# PowerSupply.net
KiCad netlist of a schematic drawn in Altium Designer
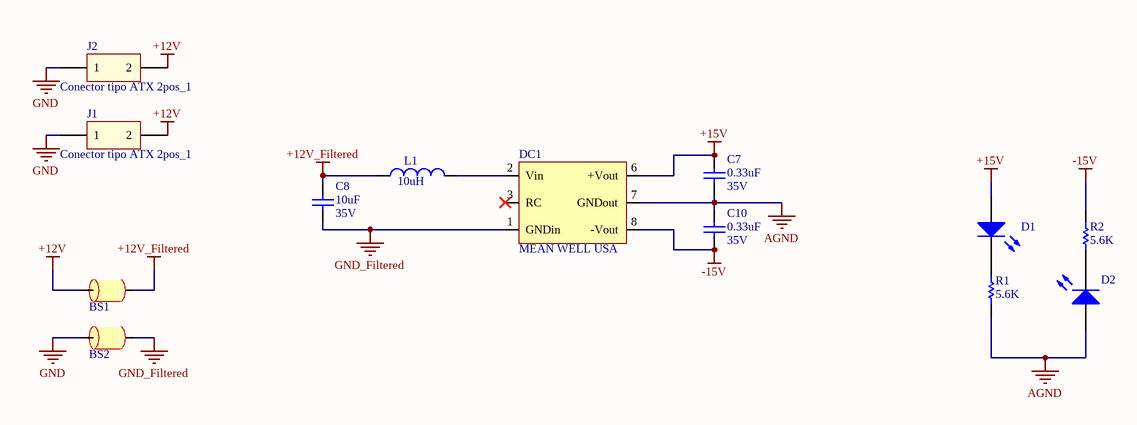
[diagram p0: PowerSupply.SchDoc]

(export (version "E")
  (design (tool "Eeschema 10.0.6"))
  (components
    (comp (ref "BS1")
      (value "Ferrite bead")
      (footprint "RES_1206")
      (description "4A")
      (libsource (lib "Componentes_SOC") (part "Bead"))
    )
    (comp (ref "BS2")
      (value "Ferrite bead")
      (footprint "RES_1206")
      (description "4A")
      (libsource (lib "Componentes_SOC") (part "Bead"))
    )
    (comp (ref "C7")
      (value "0.33uF")
      (footprint "CAP_0603")
      (description "Capacitor Ceramic")
      (fields (field (name "VOLTAGE") "35V"))
      (libsource (lib "Componentes_SOC") (part "Cap_0603"))
    )
    (comp (ref "C8")
      (value "10uF")
      (footprint "CAP_0805")
      (description "Capacitor")
      (fields (field (name "VOLTAGE") "35V"))
      (libsource (lib "Componentes_SOC") (part "Cap_0805"))
    )
    (comp (ref "C10")
      (value "0.33uF")
      (footprint "CAP_0603")
      (description "Capacitor Ceramic")
      (fields (field (name "VOLTAGE") "35V"))
      (libsource (lib "Componentes_SOC") (part "Cap_0603"))
    )
    (comp (ref "D1")
      (value "LED")
      (footprint "LED_0805_GREEN")
      (description "LED Azul")
      (fields (field (name "PUBLISHER") "Altium Limited"))
      (libsource (lib "Componentes_SOC") (part "LED2"))
    )
    (comp (ref "D2")
      (value "LED")
      (footprint "LED_0805_GREEN")
      (description "LED Azul")
      (fields (field (name "PUBLISHER") "Altium Limited"))
      (libsource (lib "Componentes_SOC") (part "LED2"))
    )
    (comp (ref "DC1")
      (value "MEAN WELL USA")
      (footprint "DC/DC +-15V 6W")
      (description "Isolated Module DC DC Converter 2 Output 15V -15V 200mA, 200mA 9V - 36V Input")
      (libsource (lib "Componentes_SOC") (part "DC/DC +12V a +-15V 6W"))
    )
    (comp (ref "J1")
      (value "Conector tipo ATX 2pos_1")
      (footprint "Conector tipo ATX Wurth 2 posiciones - (5.5mm)")
      (description "CONN HEADER VERT 2POS 5.5MM")
      (libsource (lib "Componentes_SOC") (part "Conector tipo ATX 2pos_1"))
    )
    (comp (ref "J2")
      (value "Conector tipo ATX 2pos_1")
      (footprint "Conector tipo ATX Wurth 2 posiciones - (5.5mm)")
      (description "CONN HEADER VERT 2POS 5.5MM")
      (libsource (lib "Componentes_SOC") (part "Conector tipo ATX 2pos_1"))
    )
    (comp (ref "L1")
      (value "10uH")
      (footprint "INDUCTOR_0805")
      (description "500mA")
      (libsource (lib "Componentes_SOC") (part "Inductor_0805"))
    )
    (comp (ref "R1")
      (value "5.6K")
      (footprint "RES_0805")
      (fields (field (name "PUBLISHER") "Altium Limited"))
      (libsource (lib "Componentes_SOC") (part "Res0805"))
    )
    (comp (ref "R2")
      (value "5.6K")
      (footprint "RES_0805")
      (fields (field (name "PUBLISHER") "Altium Limited"))
      (libsource (lib "Componentes_SOC") (part "Res0805"))
    )
  )
  (nets
    (net (code "1") (name "+12V") (class "Default")
      (node (ref "BS1") (pin "1") (pintype "passive"))
      (node (ref "J1") (pin "2") (pinfunction "2_2") (pintype "passive"))
      (node (ref "J2") (pin "2") (pinfunction "2_2") (pintype "passive"))
    )
    (net (code "2") (name "+12V_Filtered") (class "Default")
      (node (ref "BS1") (pin "2") (pintype "passive"))
      (node (ref "C8") (pin "1") (pinfunction "1_1") (pintype "passive"))
      (node (ref "L1") (pin "1") (pinfunction "1_1") (pintype "passive"))
    )
    (net (code "3") (name "+15V") (class "Default")
      (node (ref "C7") (pin "1") (pinfunction "1_1") (pintype "passive"))
      (node (ref "D1") (pin "1") (pinfunction "A_1") (pintype "passive"))
      (node (ref "DC1") (pin "6") (pinfunction "+Vout_6") (pintype "passive"))
    )
    (net (code "4") (name "-15V") (class "Default")
      (node (ref "C10") (pin "2") (pinfunction "2_2") (pintype "passive"))
      (node (ref "DC1") (pin "8") (pinfunction "-Vout_8") (pintype "passive"))
      (node (ref "R2") (pin "2") (pinfunction "2_2") (pintype "passive"))
    )
    (net (code "5") (name "AGND") (class "Default")
      (node (ref "C10") (pin "1") (pinfunction "1_1") (pintype "passive"))
      (node (ref "C7") (pin "2") (pinfunction "2_2") (pintype "passive"))
      (node (ref "D2") (pin "1") (pinfunction "A_1") (pintype "passive"))
      (node (ref "DC1") (pin "7") (pinfunction "GNDout_7") (pintype "passive"))
      (node (ref "R1") (pin "1") (pinfunction "1_1") (pintype "passive"))
    )
    (net (code "6") (name "GND") (class "Default")
      (node (ref "BS2") (pin "1") (pintype "passive"))
      (node (ref "J1") (pin "1") (pinfunction "1_1") (pintype "passive"))
      (node (ref "J2") (pin "1") (pinfunction "1_1") (pintype "passive"))
    )
    (net (code "7") (name "GND_Filtered") (class "Default")
      (node (ref "BS2") (pin "2") (pintype "passive"))
      (node (ref "C8") (pin "2") (pinfunction "2_2") (pintype "passive"))
      (node (ref "DC1") (pin "1") (pinfunction "GNDin_1") (pintype "passive"))
    )
    (net (code "8") (name "Net-(D1-K)") (class "Default")
      (node (ref "D1") (pin "2") (pinfunction "K_2") (pintype "passive"))
      (node (ref "R1") (pin "2") (pinfunction "2_2") (pintype "passive"))
    )
    (net (code "9") (name "Net-(D2-K)") (class "Default")
      (node (ref "D2") (pin "2") (pinfunction "K_2") (pintype "passive"))
      (node (ref "R2") (pin "1") (pinfunction "1_1") (pintype "passive"))
    )
    (net (code "10") (name "Net-(DC1-Vin)") (class "Default")
      (node (ref "DC1") (pin "2") (pinfunction "Vin_2") (pintype "passive"))
      (node (ref "L1") (pin "2") (pinfunction "2_2") (pintype "passive"))
    )
    (net (code "11") (name "unconnected-(DC1-NC-Pad15)") (class "Default")
      (node (ref "DC1") (pin "15") (pinfunction "NC_15") (pintype "passive"))
    )
    (net (code "12") (name "unconnected-(DC1-NC-Pad16)") (class "Default")
      (node (ref "DC1") (pin "16") (pinfunction "NC_16") (pintype "passive"))
    )
    (net (code "13") (name "unconnected-(DC1-NC-Pad17)") (class "Default")
      (node (ref "DC1") (pin "17") (pinfunction "NC_17") (pintype "passive"))
    )
    (net (code "14") (name "unconnected-(DC1-NC-Pad26)") (class "Default")
      (node (ref "DC1") (pin "26") (pinfunction "NC_26") (pintype "passive"))
    )
    (net (code "15") (name "unconnected-(DC1-NC-Pad27)") (class "Default")
      (node (ref "DC1") (pin "27") (pinfunction "NC_27") (pintype "passive"))
    )
    (net (code "16") (name "unconnected-(DC1-RC-Pad3)") (class "Default")
      (node (ref "DC1") (pin "3") (pinfunction "RC_3") (pintype "passive+no_connect"))
    )
  )
)
